# sensor_esp32.net
KiCad netlist of a schematic drawn in EAGLE
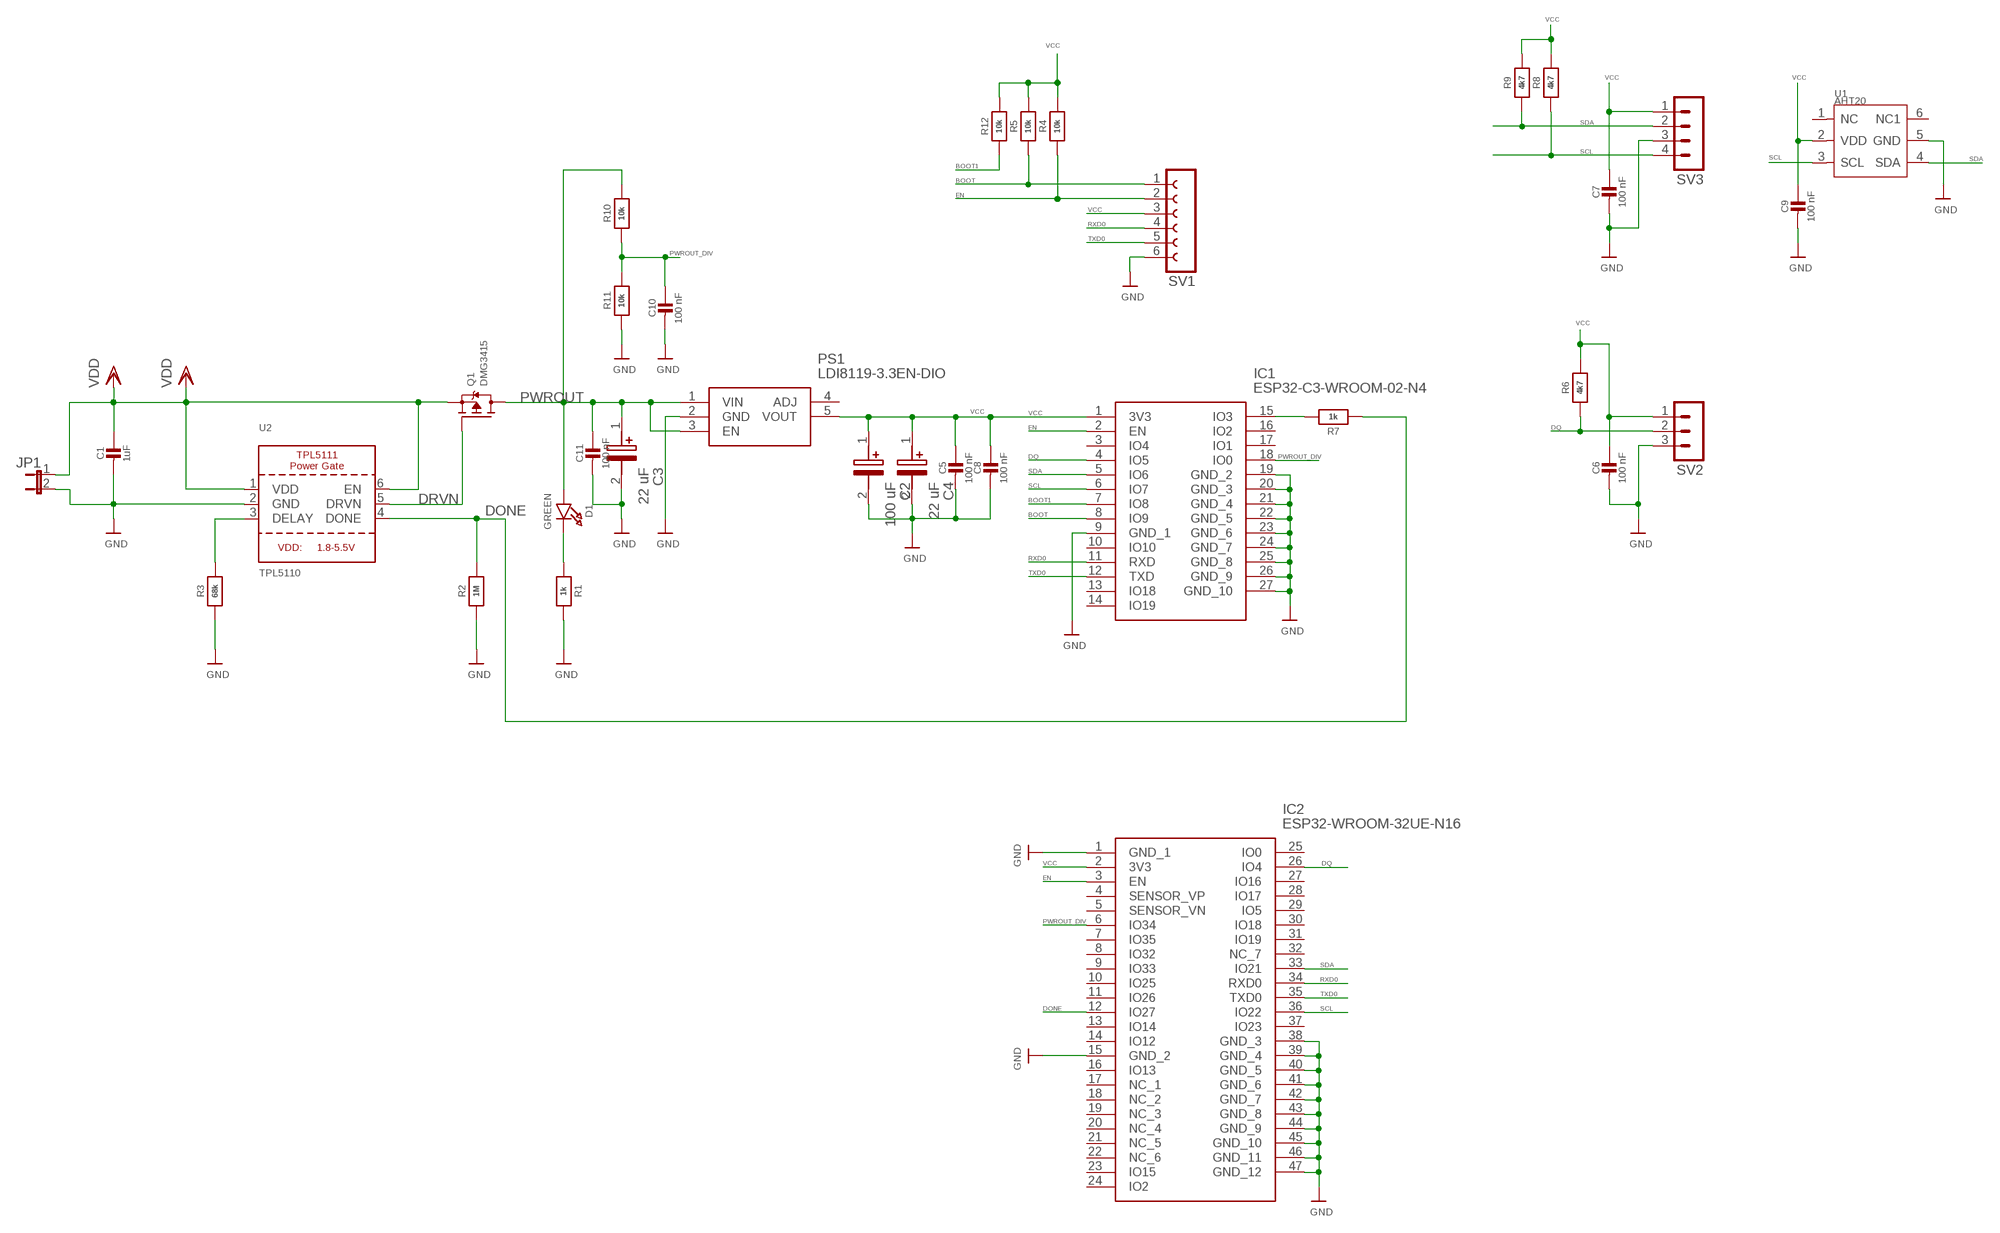
[diagram p0: schematic, sheet 1]

(export (version "E")
  (design (tool "Eeschema 10.0.6"))
  (components
    (comp (ref "C1")
      (value "1uF")
      (footprint "eagle-import:0805-NO")
      (libsource (lib "eagle-import") (part "CAP_CERAMIC0805-NOOUTLINE"))
    )
    (comp (ref "C2")
      (value "100 uF")
      (footprint "eagle-import:CAPPM6032X280N")
      (fields (field (name "MANUFACTURER_PART_NUMBER") "293D107X9010C2TE3"))
      (libsource (lib "eagle-import") (part "293D107X9010C2TE3"))
    )
    (comp (ref "C3")
      (value "22 uF")
      (footprint "eagle-import:CAPPM3216X180N")
      (description "Solid Tantalum Surface Mount Chip Capacitors TANTAMOUNT(TM), Molded Case, Standard Industrial Grade")
      (fields
        (field (name "MANUFACTURER_PART_NUMBER") "293D226X9010A2TE3")
        (field (name "HEIGHT") "1.8mm")
        (field (name "MANUFACTURER_NAME") "Vishay")
        (field (name "MANUFACTURER_PART_NUMBER_1") "293D226X9010A2TE3")
      )
      (libsource (lib "eagle-import") (part "293D226X9010A2TE3"))
    )
    (comp (ref "C4")
      (value "22 uF")
      (footprint "eagle-import:CAPPM3216X180N")
      (description "Solid Tantalum Surface Mount Chip Capacitors TANTAMOUNT(TM), Molded Case, Standard Industrial Grade")
      (fields
        (field (name "MANUFACTURER_PART_NUMBER") "293D226X9010A2TE3")
        (field (name "HEIGHT") "1.8mm")
        (field (name "MANUFACTURER_NAME") "Vishay")
        (field (name "MANUFACTURER_PART_NUMBER_1") "293D226X9010A2TE3")
      )
      (libsource (lib "eagle-import") (part "293D226X9010A2TE3"))
    )
    (comp (ref "C5")
      (value "100 nF")
      (footprint "eagle-import:_0603")
      (libsource (lib "eagle-import") (part "CAP_CERAMIC_0603"))
    )
    (comp (ref "C6")
      (value "100 nF")
      (footprint "eagle-import:_0603")
      (libsource (lib "eagle-import") (part "CAP_CERAMIC_0603"))
    )
    (comp (ref "C7")
      (value "100 nF")
      (footprint "eagle-import:_0603")
      (libsource (lib "eagle-import") (part "CAP_CERAMIC_0603"))
    )
    (comp (ref "C8")
      (value "100 nF")
      (footprint "eagle-import:_0603")
      (libsource (lib "eagle-import") (part "CAP_CERAMIC_0603"))
    )
    (comp (ref "C9")
      (value "100 nF")
      (footprint "eagle-import:_0603")
      (libsource (lib "eagle-import") (part "CAP_CERAMIC_0603"))
    )
    (comp (ref "C10")
      (value "100 nF")
      (footprint "eagle-import:_0603")
      (libsource (lib "eagle-import") (part "CAP_CERAMIC_0603"))
    )
    (comp (ref "C11")
      (value "100 nF")
      (footprint "eagle-import:_0603")
      (libsource (lib "eagle-import") (part "CAP_CERAMIC_0603"))
    )
    (comp (ref "D1")
      (value "GREEN")
      (footprint "eagle-import:CHIPLED_0805_NOOUTLINE")
      (libsource (lib "eagle-import") (part "LED0805_NOOUTLINE"))
    )
    (comp (ref "IC1")
      (value "ESP32-C3-WROOM-02-N4")
      (footprint "eagle-import:ESP32C3WROOM02N4")
      (libsource (lib "eagle-import") (part "ESP32-C3-WROOM-02-N4"))
    )
    (comp (ref "IC2")
      (value "ESP32-WROOM-32UE-N16")
      (footprint "eagle-import:ESP32WROOM32UEN16")
      (libsource (lib "eagle-import") (part "ESP32-WROOM-32UE-N16"))
    )
    (comp (ref "JP1")
      (value "JP1E")
      (footprint "eagle-import:JP1")
      (libsource (lib "eagle-import") (part "JP1E"))
    )
    (comp (ref "PS1")
      (value "LDI8119-3.3EN-DIO")
      (footprint "eagle-import:SOT95P282X145-5N")
      (fields (field (name "MANUFACTURER_PART_NUMBER") "AP2202K-3.3TRG1"))
      (libsource (lib "eagle-import") (part "AP2202K-3.3TRG1"))
    )
    (comp (ref "Q1")
      (value "DMG3415")
      (footprint "eagle-import:SOT23-WIDE")
      (libsource (lib "eagle-import") (part "MOSFET-PWIDE"))
    )
    (comp (ref "R1")
      (value "1k")
      (footprint "eagle-import:_0603")
      (libsource (lib "eagle-import") (part "RESISTOR_0603"))
    )
    (comp (ref "R2")
      (value "1M")
      (footprint "eagle-import:_0603")
      (libsource (lib "eagle-import") (part "RESISTOR_0603"))
    )
    (comp (ref "R3")
      (value "68k")
      (footprint "eagle-import:_0603")
      (libsource (lib "eagle-import") (part "RESISTOR_0603"))
    )
    (comp (ref "R4")
      (value "10k")
      (footprint "eagle-import:_0603")
      (libsource (lib "eagle-import") (part "RESISTOR_0603"))
    )
    (comp (ref "R5")
      (value "10k")
      (footprint "eagle-import:_0603")
      (libsource (lib "eagle-import") (part "RESISTOR_0603"))
    )
    (comp (ref "R6")
      (value "4k7")
      (footprint "eagle-import:_0603")
      (libsource (lib "eagle-import") (part "RESISTOR_0603"))
    )
    (comp (ref "R7")
      (value "1k")
      (footprint "eagle-import:_0603")
      (libsource (lib "eagle-import") (part "RESISTOR_0603"))
    )
    (comp (ref "R8")
      (value "4k7")
      (footprint "eagle-import:_0603")
      (libsource (lib "eagle-import") (part "RESISTOR_0603"))
    )
    (comp (ref "R9")
      (value "4k7")
      (footprint "eagle-import:_0603")
      (libsource (lib "eagle-import") (part "RESISTOR_0603"))
    )
    (comp (ref "R10")
      (value "10k")
      (footprint "eagle-import:_0603")
      (libsource (lib "eagle-import") (part "RESISTOR_0603"))
    )
    (comp (ref "R11")
      (value "10k")
      (footprint "eagle-import:_0603")
      (libsource (lib "eagle-import") (part "RESISTOR_0603"))
    )
    (comp (ref "R12")
      (value "10k")
      (footprint "eagle-import:_0603")
      (libsource (lib "eagle-import") (part "RESISTOR_0603"))
    )
    (comp (ref "SV1")
      (value "FE06-1")
      (footprint "eagle-import:FE06")
      (libsource (lib "eagle-import") (part "FE06-1"))
    )
    (comp (ref "SV2")
      (value "MA03-1")
      (footprint "eagle-import:MA03-1")
      (libsource (lib "eagle-import") (part "MA03-1"))
    )
    (comp (ref "SV3")
      (value "MA04-1")
      (footprint "eagle-import:MA04-1")
      (libsource (lib "eagle-import") (part "MA04-1"))
    )
    (comp (ref "U1")
      (value "AHT20")
      (footprint "eagle-import:SNR6-1.0-3X3X1MM")
      (libsource (lib "eagle-import") (part "SENSOR-AHT20"))
    )
    (comp (ref "U2")
      (value "TPL5110")
      (footprint "eagle-import:SOT23-6")
      (libsource (lib "eagle-import") (part "TPL5111"))
    )
  )
  (nets
    (net (code "1") (name "/BOOT") (class "Default")
      (node (ref "IC1") (pin "8") (pinfunction "IO9_8") (pintype "bidirectional"))
      (node (ref "R5") (pin "1") (pinfunction "1_1") (pintype "passive"))
      (node (ref "SV1") (pin "1") (pinfunction "1_1") (pintype "passive"))
    )
    (net (code "2") (name "/BOOT1") (class "Default")
      (node (ref "IC1") (pin "7") (pinfunction "IO8_7") (pintype "bidirectional"))
      (node (ref "R12") (pin "1") (pinfunction "1_1") (pintype "passive"))
    )
    (net (code "3") (name "/DONE") (class "Default")
      (node (ref "IC2") (pin "12") (pinfunction "IO27_12") (pintype "bidirectional"))
      (node (ref "R2") (pin "2") (pinfunction "2_2") (pintype "passive"))
      (node (ref "R7") (pin "1") (pinfunction "1_1") (pintype "passive"))
      (node (ref "U2") (pin "4") (pinfunction "DONE_4") (pintype "input"))
    )
    (net (code "4") (name "/DQ") (class "Default")
      (node (ref "IC1") (pin "4") (pinfunction "IO5_4") (pintype "bidirectional"))
      (node (ref "IC2") (pin "26") (pinfunction "IO4_26") (pintype "bidirectional"))
      (node (ref "R6") (pin "1") (pinfunction "1_1") (pintype "passive"))
      (node (ref "SV2") (pin "2") (pinfunction "2_2") (pintype "passive"))
    )
    (net (code "5") (name "/DRVN") (class "Default")
      (node (ref "Q1") (pin "1") (pinfunction "G_1") (pintype "passive"))
      (node (ref "U2") (pin "5") (pinfunction "DRVN_5") (pintype "output"))
    )
    (net (code "6") (name "/EN") (class "Default")
      (node (ref "IC1") (pin "2") (pinfunction "EN_2") (pintype "bidirectional"))
      (node (ref "IC2") (pin "3") (pinfunction "EN_3") (pintype "bidirectional"))
      (node (ref "R4") (pin "1") (pinfunction "1_1") (pintype "passive"))
      (node (ref "SV1") (pin "2") (pinfunction "2_2") (pintype "passive"))
    )
    (net (code "7") (name "/PWROUT") (class "Default")
      (node (ref "C11") (pin "1") (pinfunction "1_1") (pintype "passive"))
      (node (ref "C3") (pin "1") (pinfunction "+_1") (pintype "bidirectional"))
      (node (ref "D1") (pin "A") (pinfunction "A_A") (pintype "passive"))
      (node (ref "PS1") (pin "1") (pinfunction "VIN_1") (pintype "bidirectional"))
      (node (ref "PS1") (pin "3") (pinfunction "EN_3") (pintype "bidirectional"))
      (node (ref "Q1") (pin "3") (pinfunction "D_3") (pintype "passive"))
      (node (ref "R10") (pin "2") (pinfunction "2_2") (pintype "passive"))
    )
    (net (code "8") (name "/PWROUT_DIV") (class "Default")
      (node (ref "C10") (pin "1") (pinfunction "1_1") (pintype "passive"))
      (node (ref "IC1") (pin "18") (pinfunction "IO0_18") (pintype "bidirectional"))
      (node (ref "IC2") (pin "6") (pinfunction "IO34_6") (pintype "bidirectional"))
      (node (ref "R10") (pin "1") (pinfunction "1_1") (pintype "passive"))
      (node (ref "R11") (pin "2") (pinfunction "2_2") (pintype "passive"))
    )
    (net (code "9") (name "/RXD0") (class "Default")
      (node (ref "IC1") (pin "11") (pinfunction "RXD_11") (pintype "bidirectional"))
      (node (ref "IC2") (pin "34") (pinfunction "RXD0_34") (pintype "bidirectional"))
      (node (ref "SV1") (pin "4") (pinfunction "4_4") (pintype "passive"))
    )
    (net (code "10") (name "/SCL") (class "Default")
      (node (ref "IC1") (pin "6") (pinfunction "IO7_6") (pintype "bidirectional"))
      (node (ref "IC2") (pin "36") (pinfunction "IO22_36") (pintype "bidirectional"))
      (node (ref "R8") (pin "1") (pinfunction "1_1") (pintype "passive"))
      (node (ref "SV3") (pin "4") (pinfunction "4_4") (pintype "passive"))
      (node (ref "U1") (pin "3") (pinfunction "SCL_3") (pintype "bidirectional"))
    )
    (net (code "11") (name "/SDA") (class "Default")
      (node (ref "IC1") (pin "5") (pinfunction "IO6_5") (pintype "bidirectional"))
      (node (ref "IC2") (pin "33") (pinfunction "IO21_33") (pintype "bidirectional"))
      (node (ref "R9") (pin "1") (pinfunction "1_1") (pintype "passive"))
      (node (ref "SV3") (pin "2") (pinfunction "2_2") (pintype "passive"))
      (node (ref "U1") (pin "4") (pinfunction "SDA_4") (pintype "bidirectional"))
    )
    (net (code "12") (name "/TXD0") (class "Default")
      (node (ref "IC1") (pin "12") (pinfunction "TXD_12") (pintype "bidirectional"))
      (node (ref "IC2") (pin "35") (pinfunction "TXD0_35") (pintype "bidirectional"))
      (node (ref "SV1") (pin "5") (pinfunction "5_5") (pintype "passive"))
    )
    (net (code "13") (name "/VCC") (class "Default")
      (node (ref "C2") (pin "1") (pinfunction "+_1") (pintype "bidirectional"))
      (node (ref "C4") (pin "1") (pinfunction "+_1") (pintype "bidirectional"))
      (node (ref "C5") (pin "1") (pinfunction "1_1") (pintype "passive"))
      (node (ref "C6") (pin "1") (pinfunction "1_1") (pintype "passive"))
      (node (ref "C7") (pin "1") (pinfunction "1_1") (pintype "passive"))
      (node (ref "C8") (pin "1") (pinfunction "1_1") (pintype "passive"))
      (node (ref "C9") (pin "1") (pinfunction "1_1") (pintype "passive"))
      (node (ref "IC1") (pin "1") (pinfunction "3V3_1") (pintype "bidirectional"))
      (node (ref "IC2") (pin "2") (pinfunction "3V3_2") (pintype "bidirectional"))
      (node (ref "PS1") (pin "5") (pinfunction "VOUT_5") (pintype "bidirectional"))
      (node (ref "R12") (pin "2") (pinfunction "2_2") (pintype "passive"))
      (node (ref "R4") (pin "2") (pinfunction "2_2") (pintype "passive"))
      (node (ref "R5") (pin "2") (pinfunction "2_2") (pintype "passive"))
      (node (ref "R6") (pin "2") (pinfunction "2_2") (pintype "passive"))
      (node (ref "R8") (pin "2") (pinfunction "2_2") (pintype "passive"))
      (node (ref "R9") (pin "2") (pinfunction "2_2") (pintype "passive"))
      (node (ref "SV1") (pin "3") (pinfunction "3_3") (pintype "passive"))
      (node (ref "SV2") (pin "1") (pinfunction "1_1") (pintype "passive"))
      (node (ref "SV3") (pin "1") (pinfunction "1_1") (pintype "passive"))
      (node (ref "U1") (pin "2") (pinfunction "VDD_2") (pintype "bidirectional"))
    )
    (net (code "14") (name "GND") (class "Default")
      (node (ref "C1") (pin "2") (pinfunction "2_2") (pintype "passive"))
      (node (ref "C10") (pin "2") (pinfunction "2_2") (pintype "passive"))
      (node (ref "C11") (pin "2") (pinfunction "2_2") (pintype "passive"))
      (node (ref "C2") (pin "2") (pinfunction "-_2") (pintype "bidirectional"))
      (node (ref "C3") (pin "2") (pinfunction "-_2") (pintype "bidirectional"))
      (node (ref "C4") (pin "2") (pinfunction "-_2") (pintype "bidirectional"))
      (node (ref "C5") (pin "2") (pinfunction "2_2") (pintype "passive"))
      (node (ref "C6") (pin "2") (pinfunction "2_2") (pintype "passive"))
      (node (ref "C7") (pin "2") (pinfunction "2_2") (pintype "passive"))
      (node (ref "C8") (pin "2") (pinfunction "2_2") (pintype "passive"))
      (node (ref "C9") (pin "2") (pinfunction "2_2") (pintype "passive"))
      (node (ref "IC1") (pin "19") (pinfunction "GND_2_19") (pintype "bidirectional"))
      (node (ref "IC1") (pin "20") (pinfunction "GND_3_20") (pintype "bidirectional"))
      (node (ref "IC1") (pin "21") (pinfunction "GND_4_21") (pintype "bidirectional"))
      (node (ref "IC1") (pin "22") (pinfunction "GND_5_22") (pintype "bidirectional"))
      (node (ref "IC1") (pin "23") (pinfunction "GND_6_23") (pintype "bidirectional"))
      (node (ref "IC1") (pin "24") (pinfunction "GND_7_24") (pintype "bidirectional"))
      (node (ref "IC1") (pin "25") (pinfunction "GND_8_25") (pintype "bidirectional"))
      (node (ref "IC1") (pin "26") (pinfunction "GND_9_26") (pintype "bidirectional"))
      (node (ref "IC1") (pin "27") (pinfunction "GND_10_27") (pintype "bidirectional"))
      (node (ref "IC1") (pin "9") (pinfunction "GND_1_9") (pintype "bidirectional"))
      (node (ref "IC2") (pin "1") (pinfunction "GND_1_1") (pintype "bidirectional"))
      (node (ref "IC2") (pin "15") (pinfunction "GND_2_15") (pintype "bidirectional"))
      (node (ref "IC2") (pin "38") (pinfunction "GND_3_38") (pintype "bidirectional"))
      (node (ref "IC2") (pin "39") (pinfunction "GND_4_39") (pintype "bidirectional"))
      (node (ref "IC2") (pin "40") (pinfunction "GND_5_40") (pintype "bidirectional"))
      (node (ref "IC2") (pin "41") (pinfunction "GND_6_41") (pintype "bidirectional"))
      (node (ref "IC2") (pin "42") (pinfunction "GND_7_42") (pintype "bidirectional"))
      (node (ref "IC2") (pin "43") (pinfunction "GND_8_43") (pintype "bidirectional"))
      (node (ref "IC2") (pin "44") (pinfunction "GND_9_44") (pintype "bidirectional"))
      (node (ref "IC2") (pin "45") (pinfunction "GND_10_45") (pintype "bidirectional"))
      (node (ref "IC2") (pin "46") (pinfunction "GND_11_46") (pintype "bidirectional"))
      (node (ref "IC2") (pin "47") (pinfunction "GND_12_47") (pintype "bidirectional"))
      (node (ref "JP1") (pin "2") (pinfunction "2_2") (pintype "passive"))
      (node (ref "PS1") (pin "2") (pinfunction "GND_2") (pintype "bidirectional"))
      (node (ref "R1") (pin "2") (pinfunction "2_2") (pintype "passive"))
      (node (ref "R11") (pin "1") (pinfunction "1_1") (pintype "passive"))
      (node (ref "R2") (pin "1") (pinfunction "1_1") (pintype "passive"))
      (node (ref "R3") (pin "1") (pinfunction "1_1") (pintype "passive"))
      (node (ref "SV1") (pin "6") (pinfunction "6_6") (pintype "passive"))
      (node (ref "SV2") (pin "3") (pinfunction "3_3") (pintype "passive"))
      (node (ref "SV3") (pin "3") (pinfunction "3_3") (pintype "passive"))
      (node (ref "U1") (pin "5") (pinfunction "GND_5") (pintype "bidirectional"))
      (node (ref "U2") (pin "2") (pinfunction "GND_2") (pintype "power_in"))
    )
    (net (code "15") (name "Net-(D1-PadC)") (class "Default")
      (node (ref "D1") (pin "C") (pinfunction "C_C") (pintype "passive"))
      (node (ref "R1") (pin "1") (pinfunction "1_1") (pintype "passive"))
    )
    (net (code "16") (name "Net-(IC1-IO3)") (class "Default")
      (node (ref "IC1") (pin "15") (pinfunction "IO3_15") (pintype "bidirectional"))
      (node (ref "R7") (pin "2") (pinfunction "2_2") (pintype "passive"))
    )
    (net (code "17") (name "Net-(U2-DELAY)") (class "Default")
      (node (ref "R3") (pin "2") (pinfunction "2_2") (pintype "passive"))
      (node (ref "U2") (pin "3") (pinfunction "DELAY_3") (pintype "input"))
    )
    (net (code "18") (name "VDD") (class "Default")
      (node (ref "C1") (pin "1") (pinfunction "1_1") (pintype "passive"))
      (node (ref "JP1") (pin "1") (pinfunction "1_1") (pintype "passive"))
      (node (ref "Q1") (pin "2") (pinfunction "S_2") (pintype "passive"))
      (node (ref "U2") (pin "1") (pinfunction "VDD_1") (pintype "power_in"))
      (node (ref "U2") (pin "6") (pinfunction "EN_6") (pintype "input"))
    )
    (net (code "19") (name "unconnected-(IC1-IO1-Pad17)") (class "Default")
      (node (ref "IC1") (pin "17") (pinfunction "IO1_17") (pintype "bidirectional"))
    )
    (net (code "20") (name "unconnected-(IC1-IO2-Pad16)") (class "Default")
      (node (ref "IC1") (pin "16") (pinfunction "IO2_16") (pintype "bidirectional"))
    )
    (net (code "21") (name "unconnected-(IC1-IO4-Pad3)") (class "Default")
      (node (ref "IC1") (pin "3") (pinfunction "IO4_3") (pintype "bidirectional"))
    )
    (net (code "22") (name "unconnected-(IC1-IO10-Pad10)") (class "Default")
      (node (ref "IC1") (pin "10") (pinfunction "IO10_10") (pintype "bidirectional"))
    )
    (net (code "23") (name "unconnected-(IC1-IO18-Pad13)") (class "Default")
      (node (ref "IC1") (pin "13") (pinfunction "IO18_13") (pintype "bidirectional"))
    )
    (net (code "24") (name "unconnected-(IC1-IO19-Pad14)") (class "Default")
      (node (ref "IC1") (pin "14") (pinfunction "IO19_14") (pintype "bidirectional"))
    )
    (net (code "25") (name "unconnected-(IC2-IO0-Pad25)") (class "Default")
      (node (ref "IC2") (pin "25") (pinfunction "IO0_25") (pintype "bidirectional"))
    )
    (net (code "26") (name "unconnected-(IC2-IO2-Pad24)") (class "Default")
      (node (ref "IC2") (pin "24") (pinfunction "IO2_24") (pintype "bidirectional"))
    )
    (net (code "27") (name "unconnected-(IC2-IO5-Pad29)") (class "Default")
      (node (ref "IC2") (pin "29") (pinfunction "IO5_29") (pintype "bidirectional"))
    )
    (net (code "28") (name "unconnected-(IC2-IO12-Pad14)") (class "Default")
      (node (ref "IC2") (pin "14") (pinfunction "IO12_14") (pintype "bidirectional"))
    )
    (net (code "29") (name "unconnected-(IC2-IO13-Pad16)") (class "Default")
      (node (ref "IC2") (pin "16") (pinfunction "IO13_16") (pintype "bidirectional"))
    )
    (net (code "30") (name "unconnected-(IC2-IO14-Pad13)") (class "Default")
      (node (ref "IC2") (pin "13") (pinfunction "IO14_13") (pintype "bidirectional"))
    )
    (net (code "31") (name "unconnected-(IC2-IO15-Pad23)") (class "Default")
      (node (ref "IC2") (pin "23") (pinfunction "IO15_23") (pintype "bidirectional"))
    )
    (net (code "32") (name "unconnected-(IC2-IO16-Pad27)") (class "Default")
      (node (ref "IC2") (pin "27") (pinfunction "IO16_27") (pintype "bidirectional"))
    )
    (net (code "33") (name "unconnected-(IC2-IO17-Pad28)") (class "Default")
      (node (ref "IC2") (pin "28") (pinfunction "IO17_28") (pintype "bidirectional"))
    )
    (net (code "34") (name "unconnected-(IC2-IO18-Pad30)") (class "Default")
      (node (ref "IC2") (pin "30") (pinfunction "IO18_30") (pintype "bidirectional"))
    )
    (net (code "35") (name "unconnected-(IC2-IO19-Pad31)") (class "Default")
      (node (ref "IC2") (pin "31") (pinfunction "IO19_31") (pintype "bidirectional"))
    )
    (net (code "36") (name "unconnected-(IC2-IO23-Pad37)") (class "Default")
      (node (ref "IC2") (pin "37") (pinfunction "IO23_37") (pintype "bidirectional"))
    )
    (net (code "37") (name "unconnected-(IC2-IO25-Pad10)") (class "Default")
      (node (ref "IC2") (pin "10") (pinfunction "IO25_10") (pintype "bidirectional"))
    )
    (net (code "38") (name "unconnected-(IC2-IO26-Pad11)") (class "Default")
      (node (ref "IC2") (pin "11") (pinfunction "IO26_11") (pintype "bidirectional"))
    )
    (net (code "39") (name "unconnected-(IC2-IO32-Pad8)") (class "Default")
      (node (ref "IC2") (pin "8") (pinfunction "IO32_8") (pintype "bidirectional"))
    )
    (net (code "40") (name "unconnected-(IC2-IO33-Pad9)") (class "Default")
      (node (ref "IC2") (pin "9") (pinfunction "IO33_9") (pintype "bidirectional"))
    )
    (net (code "41") (name "unconnected-(IC2-IO35-Pad7)") (class "Default")
      (node (ref "IC2") (pin "7") (pinfunction "IO35_7") (pintype "bidirectional"))
    )
    (net (code "42") (name "unconnected-(IC2-NC_1-Pad17)") (class "Default")
      (node (ref "IC2") (pin "17") (pinfunction "NC_1_17") (pintype "bidirectional"))
    )
    (net (code "43") (name "unconnected-(IC2-NC_2-Pad18)") (class "Default")
      (node (ref "IC2") (pin "18") (pinfunction "NC_2_18") (pintype "bidirectional"))
    )
    (net (code "44") (name "unconnected-(IC2-NC_3-Pad19)") (class "Default")
      (node (ref "IC2") (pin "19") (pinfunction "NC_3_19") (pintype "bidirectional"))
    )
    (net (code "45") (name "unconnected-(IC2-NC_4-Pad20)") (class "Default")
      (node (ref "IC2") (pin "20") (pinfunction "NC_4_20") (pintype "bidirectional"))
    )
    (net (code "46") (name "unconnected-(IC2-NC_5-Pad21)") (class "Default")
      (node (ref "IC2") (pin "21") (pinfunction "NC_5_21") (pintype "bidirectional"))
    )
    (net (code "47") (name "unconnected-(IC2-NC_6-Pad22)") (class "Default")
      (node (ref "IC2") (pin "22") (pinfunction "NC_6_22") (pintype "bidirectional"))
    )
    (net (code "48") (name "unconnected-(IC2-NC_7-Pad32)") (class "Default")
      (node (ref "IC2") (pin "32") (pinfunction "NC_7_32") (pintype "bidirectional"))
    )
    (net (code "49") (name "unconnected-(IC2-SENSOR_VN-Pad5)") (class "Default")
      (node (ref "IC2") (pin "5") (pinfunction "SENSOR_VN_5") (pintype "bidirectional"))
    )
    (net (code "50") (name "unconnected-(IC2-SENSOR_VP-Pad4)") (class "Default")
      (node (ref "IC2") (pin "4") (pinfunction "SENSOR_VP_4") (pintype "bidirectional"))
    )
    (net (code "51") (name "unconnected-(PS1-ADJ-Pad4)") (class "Default")
      (node (ref "PS1") (pin "4") (pinfunction "ADJ_4") (pintype "bidirectional"))
    )
    (net (code "52") (name "unconnected-(U1-NC-Pad1)") (class "Default")
      (node (ref "U1") (pin "1") (pinfunction "NC_1") (pintype "bidirectional"))
    )
    (net (code "53") (name "unconnected-(U1-NC1-Pad6)") (class "Default")
      (node (ref "U1") (pin "6") (pinfunction "NC1_6") (pintype "bidirectional"))
    )
  )
)
